# digipot.net
KiCad netlist of a schematic drawn in Altium Designer
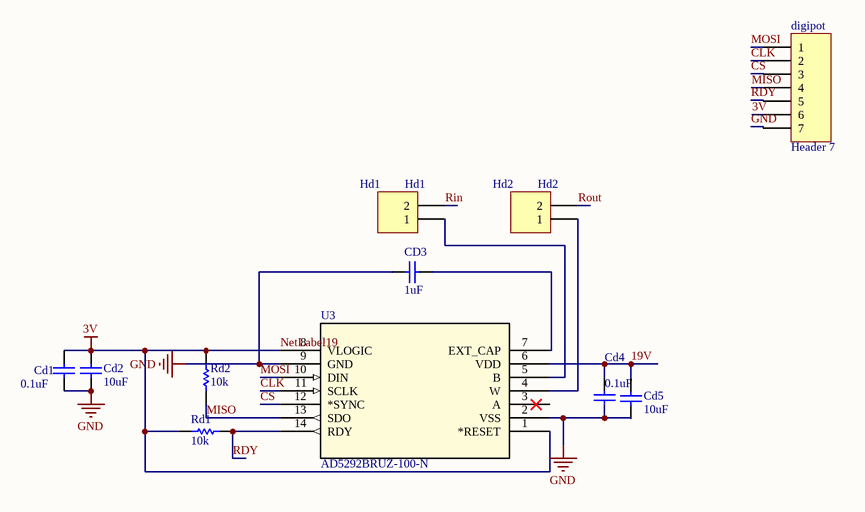
[diagram p0: digipot.SchDoc]

(export (version "E")
  (design (tool "Eeschema 10.0.6"))
  (components
    (comp (ref "Cd1")
      (value "0.1uF")
      (footprint "CC2012-0805")
      (description "Capacitor")
      (fields
        (field (name "MANUFACTURER") "Generic Components")
        (field (name "Comment") "Cap-NP")
        (field (name "PUBLISHER") "Altium Limited")
      )
      (libsource (lib "NOPPARAT_SCH_DXP") (part "Cap-NP"))
    )
    (comp (ref "Cd2")
      (value "10uF")
      (footprint "CC2012-0805")
      (description "Capacitor")
      (fields
        (field (name "MANUFACTURER") "Generic Components")
        (field (name "Comment") "Cap-NP")
        (field (name "PUBLISHER") "Altium Limited")
      )
      (libsource (lib "NOPPARAT_SCH_DXP") (part "Cap-NP"))
    )
    (comp (ref "CD3")
      (value "1uF")
      (footprint "CC2012-0805")
      (description "Capacitor")
      (fields
        (field (name "MANUFACTURER") "Generic Components")
        (field (name "Comment") "Cap-NP")
        (field (name "PUBLISHER") "Altium Limited")
      )
      (libsource (lib "NOPPARAT_SCH_DXP") (part "Cap-NP"))
    )
    (comp (ref "Cd4")
      (value "0.1uF")
      (footprint "CC2012-0805")
      (description "Capacitor")
      (fields
        (field (name "MANUFACTURER") "Generic Components")
        (field (name "Comment") "Cap-NP")
        (field (name "PUBLISHER") "Altium Limited")
      )
      (libsource (lib "NOPPARAT_SCH_DXP") (part "Cap-NP"))
    )
    (comp (ref "Cd5")
      (value "10uF")
      (footprint "CC2012-0805")
      (description "Capacitor")
      (fields
        (field (name "MANUFACTURER") "Generic Components")
        (field (name "Comment") "Cap-NP")
        (field (name "PUBLISHER") "Altium Limited")
      )
      (libsource (lib "NOPPARAT_SCH_DXP") (part "Cap-NP"))
    )
    (comp (ref "digipot")
      (value "Header 7")
      (footprint "HDR1X7")
      (description "Header, 7-Pin")
      (fields (field (name "PUBLISHER") "Altium Limited"))
      (libsource (lib "Miscellaneous Connectors") (part "Header 7"))
    )
    (comp (ref "Hd1")
      (value "Hd1")
      (footprint "HDR1X2")
      (description "Header, 2-Pin")
      (fields (field (name "PUBLISHER") "Altium Limited"))
      (libsource (lib "Miscellaneous Connectors") (part "Header 2"))
    )
    (comp (ref "Hd2")
      (value "Hd2")
      (footprint "HDR1X2")
      (description "Header, 2-Pin")
      (fields (field (name "PUBLISHER") "Altium Limited"))
      (libsource (lib "Miscellaneous Connectors") (part "Header 2"))
    )
    (comp (ref "Rd1")
      (value "10k")
      (footprint "CC2012-0805")
      (description "Resistor")
      (fields
        (field (name "MANUFACTURER") "Generic Components")
        (field (name "Comment") "Res")
        (field (name "PUBLISHER") "Altium Limited")
      )
      (libsource (lib "NOPPARAT_SCH_DXP") (part "Res"))
    )
    (comp (ref "Rd2")
      (value "10k")
      (footprint "CC2012-0805")
      (description "Resistor")
      (fields
        (field (name "MANUFACTURER") "Generic Components")
        (field (name "Comment") "Res")
        (field (name "PUBLISHER") "Altium Limited")
      )
      (libsource (lib "NOPPARAT_SCH_DXP") (part "Res"))
    )
    (comp (ref "U3")
      (value "AD5292BRUZ-100-N")
      (footprint "RU_14")
      (description "Imported")
      (fields (field (name "MANUFACTURER_PART_NUMBER") "AD5292BRUZ-100-ND"))
      (libsource (lib "AD5292BRUZ-100-ND") (part "AD5292BRUZ-100-N"))
    )
  )
  (nets
    (net (code "1") (name "/19V") (class "Default")
      (node (ref "Cd4") (pin "2") (pinfunction "2_2") (pintype "passive"))
      (node (ref "Cd5") (pin "2") (pinfunction "2_2") (pintype "passive"))
      (node (ref "U3") (pin "6") (pinfunction "VDD_6") (pintype "power_in"))
    )
    (net (code "2") (name "/CLK") (class "Default")
      (node (ref "U3") (pin "11") (pinfunction "SCLK_11") (pintype "input"))
      (node (ref "digipot") (pin "2") (pinfunction "2_2") (pintype "passive"))
    )
    (net (code "3") (name "/CS") (class "Default")
      (node (ref "U3") (pin "12") (pinfunction "*SYNC_12") (pintype "passive"))
      (node (ref "digipot") (pin "3") (pinfunction "3_3") (pintype "passive"))
    )
    (net (code "4") (name "/MISO") (class "Default")
      (node (ref "Rd2") (pin "2") (pinfunction "2_2") (pintype "passive"))
      (node (ref "U3") (pin "13") (pinfunction "SDO_13") (pintype "output"))
      (node (ref "digipot") (pin "4") (pinfunction "4_4") (pintype "passive"))
    )
    (net (code "5") (name "/MOSI") (class "Default")
      (node (ref "U3") (pin "10") (pinfunction "DIN_10") (pintype "input"))
      (node (ref "digipot") (pin "1") (pinfunction "1_1") (pintype "passive"))
    )
    (net (code "6") (name "/RDY") (class "Default")
      (node (ref "Rd1") (pin "1") (pinfunction "1_1") (pintype "passive"))
      (node (ref "U3") (pin "14") (pinfunction "RDY_14") (pintype "output"))
      (node (ref "digipot") (pin "5") (pinfunction "5_5") (pintype "passive"))
    )
    (net (code "7") (name "/Rin") (class "Default")
      (node (ref "Hd1") (pin "2") (pinfunction "2_2") (pintype "passive"))
    )
    (net (code "8") (name "/Rout") (class "Default")
      (node (ref "Hd2") (pin "2") (pinfunction "2_2") (pintype "passive"))
    )
    (net (code "9") (name "3V") (class "Default")
      (node (ref "Cd1") (pin "1") (pinfunction "1_1") (pintype "passive"))
      (node (ref "Cd2") (pin "1") (pinfunction "1_1") (pintype "passive"))
      (node (ref "Rd1") (pin "2") (pinfunction "2_2") (pintype "passive"))
      (node (ref "Rd2") (pin "1") (pinfunction "1_1") (pintype "passive"))
      (node (ref "U3") (pin "1") (pinfunction "*RESET_1") (pintype "passive"))
      (node (ref "U3") (pin "8") (pinfunction "VLOGIC_8") (pintype "power_in"))
      (node (ref "digipot") (pin "6") (pinfunction "6_6") (pintype "passive"))
    )
    (net (code "10") (name "GND") (class "Default")
      (node (ref "CD3") (pin "1") (pinfunction "1_1") (pintype "passive"))
      (node (ref "Cd1") (pin "2") (pinfunction "2_2") (pintype "passive"))
      (node (ref "Cd2") (pin "2") (pinfunction "2_2") (pintype "passive"))
      (node (ref "Cd4") (pin "1") (pinfunction "1_1") (pintype "passive"))
      (node (ref "Cd5") (pin "1") (pinfunction "1_1") (pintype "passive"))
      (node (ref "U3") (pin "2") (pinfunction "VSS_2") (pintype "power_in"))
      (node (ref "U3") (pin "9") (pinfunction "GND_9") (pintype "power_in"))
      (node (ref "digipot") (pin "7") (pinfunction "7_7") (pintype "passive"))
    )
    (net (code "11") (name "Net-(U3-B)") (class "Default")
      (node (ref "Hd1") (pin "1") (pinfunction "1_1") (pintype "passive"))
      (node (ref "U3") (pin "5") (pinfunction "B_5") (pintype "passive"))
    )
    (net (code "12") (name "Net-(U3-EXT_CAP)") (class "Default")
      (node (ref "CD3") (pin "2") (pinfunction "2_2") (pintype "passive"))
      (node (ref "U3") (pin "7") (pinfunction "EXT_CAP_7") (pintype "passive"))
    )
    (net (code "13") (name "Net-(U3-W)") (class "Default")
      (node (ref "Hd2") (pin "1") (pinfunction "1_1") (pintype "passive"))
      (node (ref "U3") (pin "4") (pinfunction "W_4") (pintype "passive"))
    )
    (net (code "14") (name "unconnected-(U3-A-Pad3)") (class "Default")
      (node (ref "U3") (pin "3") (pinfunction "A_3") (pintype "passive"))
    )
  )
)
